# f9p_rtk.net
KiCad netlist of a schematic drawn in EasyEDA
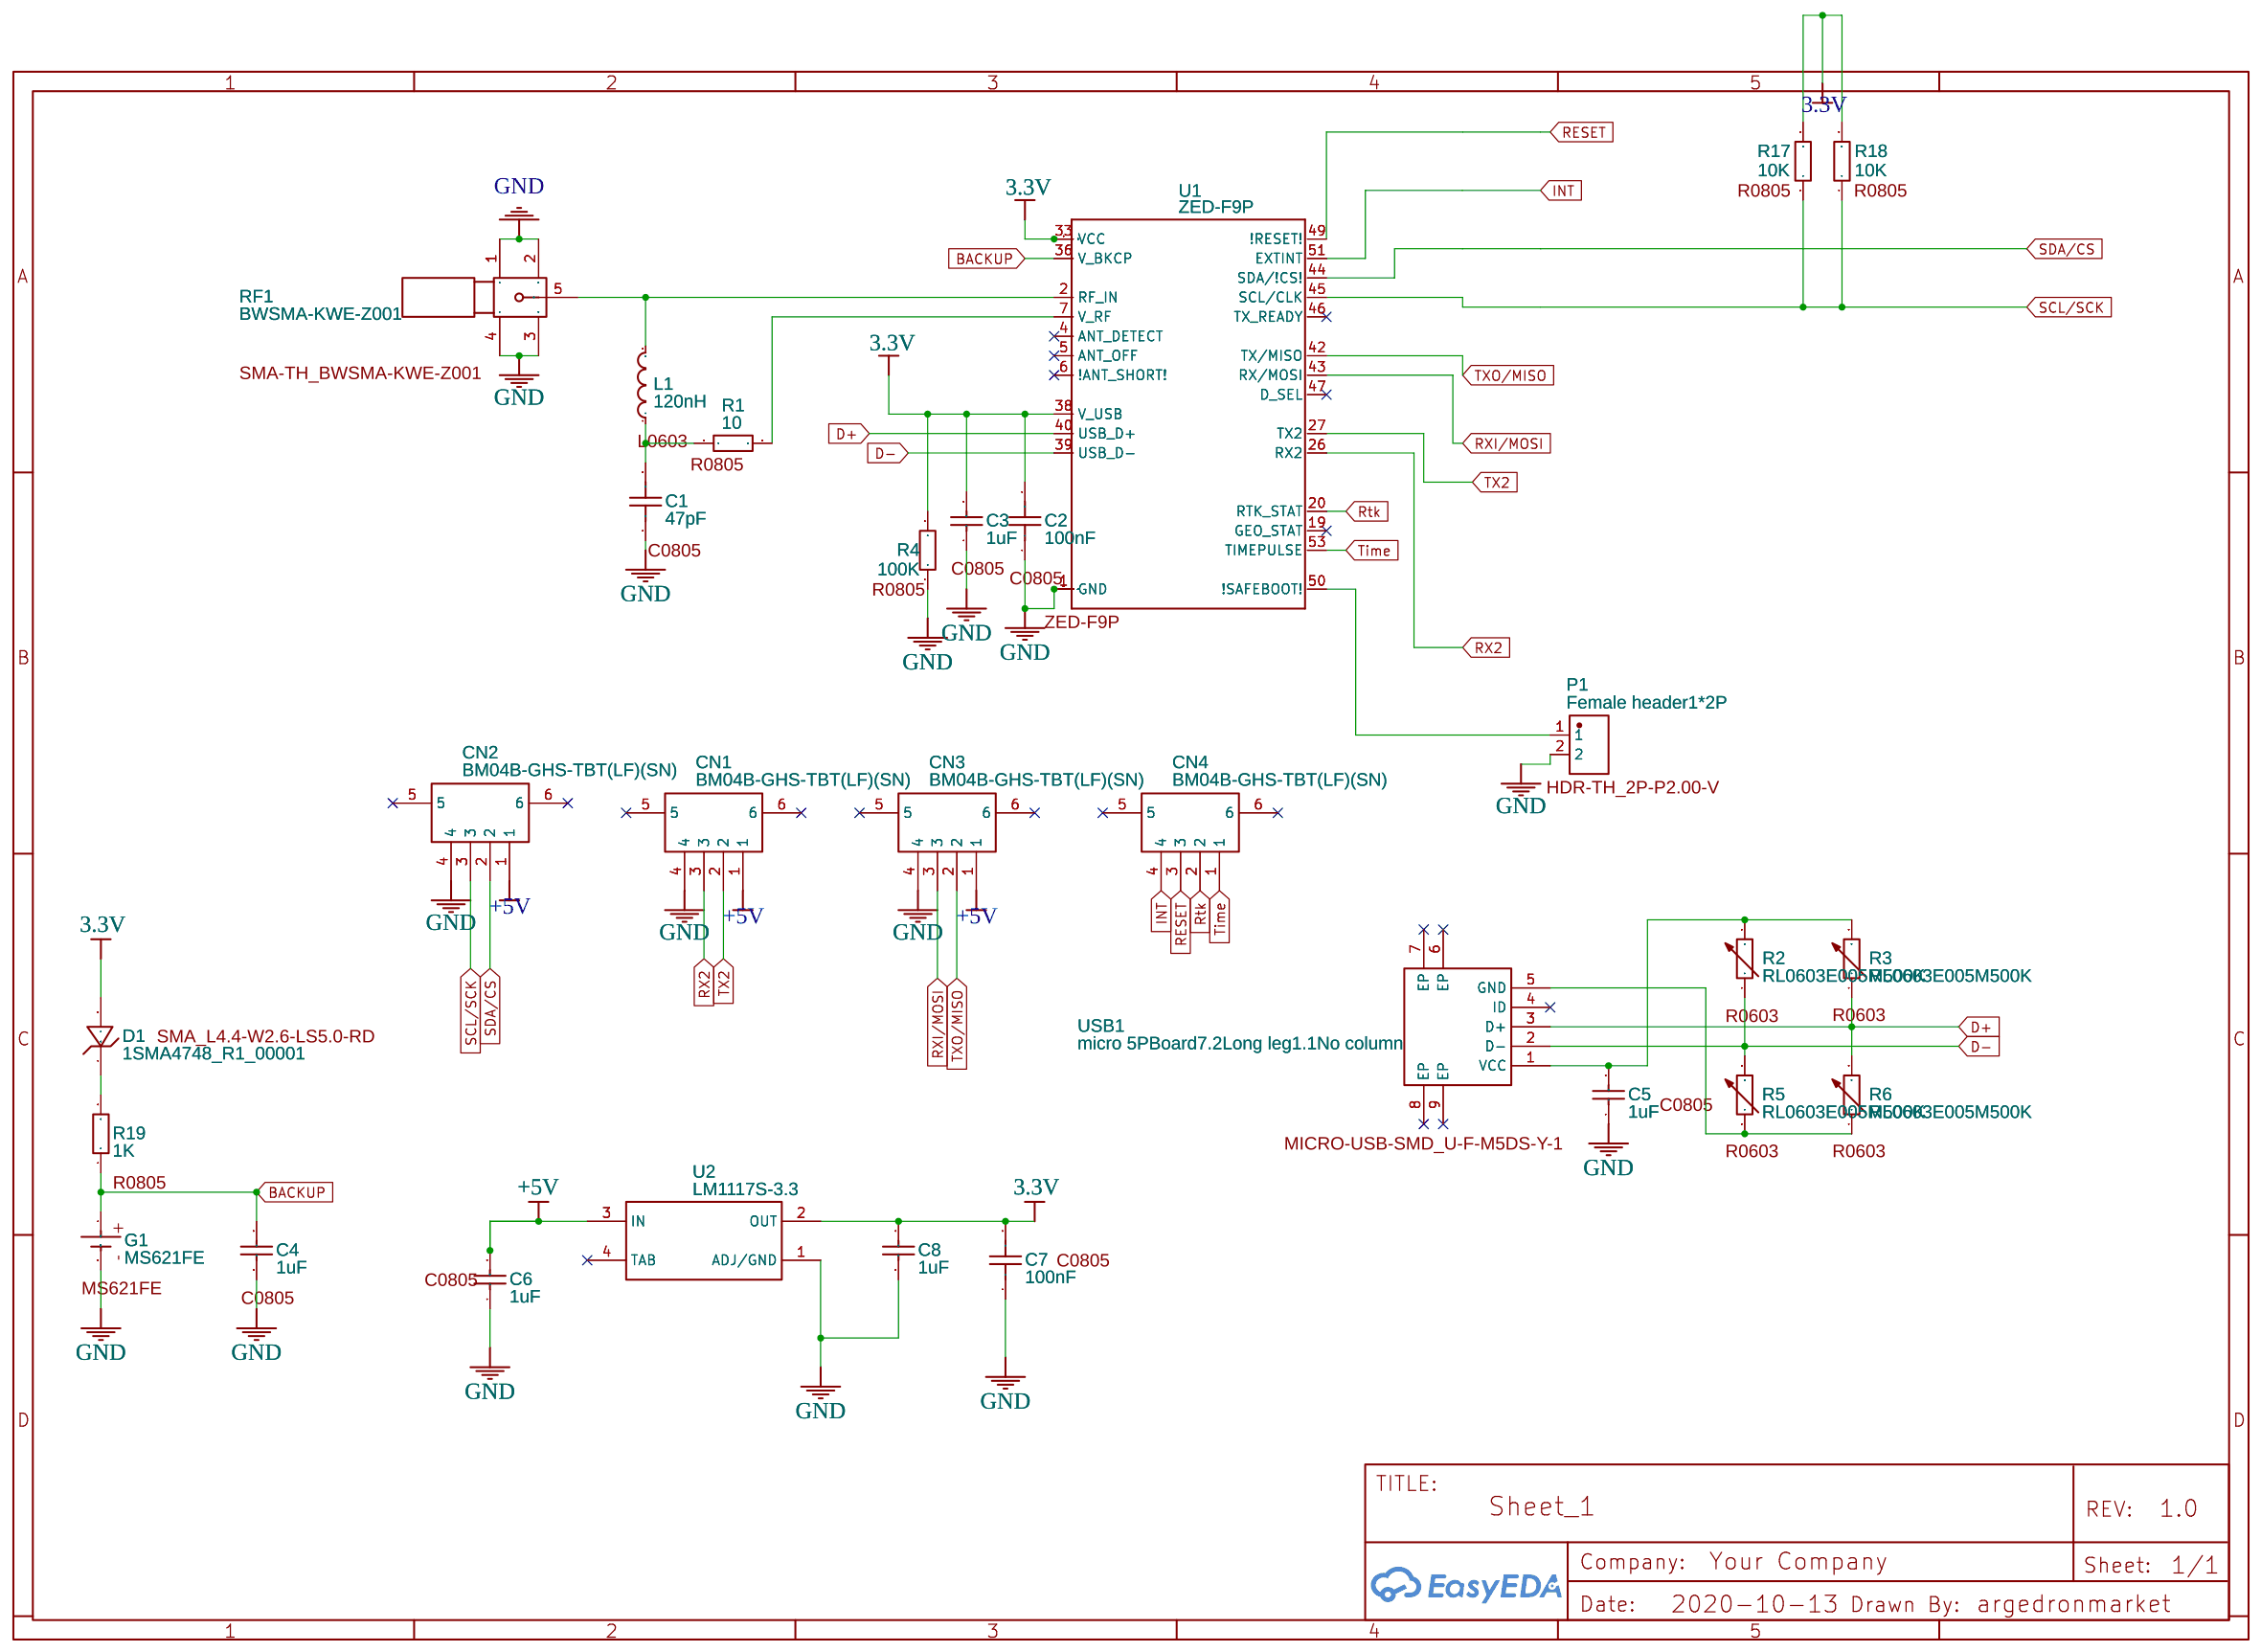
[diagram p0: schematic sheet]

(export (version "E")
  (design (tool "Eeschema 10.0.6"))
  (components
    (comp (ref "C1")
      (value "47pF")
      (fields
        (field (name "BOM_Manufacturer Part") "0805N470J500")
        (field (name "BOM_Supplier Part") "C123648")
      )
      (libsource (lib "") (part "0805N470J500"))
    )
    (comp (ref "C2")
      (value "100nF")
      (fields
        (field (name "BOM_Manufacturer Part") "TCC0805X7R104K101DT")
        (field (name "BOM_Supplier Part") "C344180")
      )
      (libsource (lib "") (part "TCC0805X7R104K101DT_1"))
    )
    (comp (ref "C3")
      (value "1uF")
      (fields
        (field (name "BOM_Manufacturer Part") "0805F105Z160")
        (field (name "BOM_Supplier Part") "C123629")
      )
      (libsource (lib "") (part "0805F105Z160"))
    )
    (comp (ref "C4")
      (value "1uF")
      (fields
        (field (name "BOM_Manufacturer Part") "0805F105Z160")
        (field (name "BOM_Supplier Part") "C123629")
      )
      (libsource (lib "") (part "0805F105Z160"))
    )
    (comp (ref "C5")
      (value "1uF")
      (fields
        (field (name "BOM_Manufacturer Part") "0805F105Z160")
        (field (name "BOM_Supplier Part") "C123629")
      )
      (libsource (lib "") (part "0805F105Z160_1"))
    )
    (comp (ref "C6")
      (value "1uF")
      (fields
        (field (name "BOM_Manufacturer Part") "0805F105Z160")
        (field (name "BOM_Supplier Part") "C123629")
      )
      (libsource (lib "") (part "0805F105Z160_2"))
    )
    (comp (ref "C7")
      (value "100nF")
      (fields
        (field (name "BOM_Manufacturer Part") "TCC0805X7R104K101DT")
        (field (name "BOM_Supplier Part") "C344180")
      )
      (libsource (lib "") (part "TCC0805X7R104K101DT"))
    )
    (comp (ref "C8")
      (value "1uF")
      (fields
        (field (name "BOM_Manufacturer Part") "0805F105Z160")
        (field (name "BOM_Supplier Part") "C123629")
      )
      (libsource (lib "") (part "0805F105Z160_3"))
    )
    (comp (ref "CN1")
      (value "BM04B-GHS-TBT(LF)(SN)")
      (fields (field (name "BOM_Supplier Part") "C161692"))
      (libsource (lib "") (part "BM04B-GHS-TBT(LF)(SN)"))
    )
    (comp (ref "CN2")
      (value "BM04B-GHS-TBT(LF)(SN)")
      (fields (field (name "BOM_Supplier Part") "C161692"))
      (libsource (lib "") (part "BM04B-GHS-TBT(LF)(SN)"))
    )
    (comp (ref "CN3")
      (value "BM04B-GHS-TBT(LF)(SN)")
      (fields (field (name "BOM_Supplier Part") "C161692"))
      (libsource (lib "") (part "BM04B-GHS-TBT(LF)(SN)"))
    )
    (comp (ref "CN4")
      (value "BM04B-GHS-TBT(LF)(SN)")
      (fields (field (name "BOM_Supplier Part") "C161692"))
      (libsource (lib "") (part "BM04B-GHS-TBT(LF)(SN)"))
    )
    (comp (ref "D1")
      (value "1SMA4748_R1_00001")
      (fields (field (name "BOM_Supplier Part") "C268431"))
      (libsource (lib "") (part "1SMA4748_R1_00001"))
    )
    (comp (ref "G1") (value "MS621FE") (libsource (lib "") (part "MS621FE")))
    (comp (ref "L1")
      (value "120nH")
      (fields
        (field (name "BOM_Manufacturer Part") "CI1608AR12K")
        (field (name "BOM_Supplier Part") "C107493")
      )
      (libsource (lib "") (part "CI1608AR12K"))
    )
    (comp (ref "P1")
      (value "Female header1*2P")
      (fields (field (name "BOM_Supplier Part") "C66509"))
      (libsource (lib "") (part "Female header1*2P"))
    )
    (comp (ref "R1")
      (value "10")
      (fields
        (field (name "BOM_Manufacturer Part") "CR0805F810R0G")
        (field (name "BOM_Supplier Part") "C101420")
      )
      (libsource (lib "") (part "CR0805F810R0G"))
    )
    (comp (ref "R2")
      (value "RL0603E005M500K")
      (fields (field (name "BOM_Supplier Part") "C20960"))
      (libsource (lib "") (part "RL0603E005M500K_1"))
    )
    (comp (ref "R3")
      (value "RL0603E005M500K")
      (fields (field (name "BOM_Supplier Part") "C20960"))
      (libsource (lib "") (part "RL0603E005M500K"))
    )
    (comp (ref "R4")
      (value "100K")
      (fields
        (field (name "BOM_Manufacturer Part") "RS-05K1003FT")
        (field (name "BOM_Supplier Part") "C118847")
      )
      (libsource (lib "") (part "RS-05K1003FT"))
    )
    (comp (ref "R5")
      (value "RL0603E005M500K")
      (fields (field (name "BOM_Supplier Part") "C20960"))
      (libsource (lib "") (part "RL0603E005M500K"))
    )
    (comp (ref "R6")
      (value "RL0603E005M500K")
      (fields (field (name "BOM_Supplier Part") "C20960"))
      (libsource (lib "") (part "RL0603E005M500K"))
    )
    (comp (ref "R17")
      (value "10K")
      (fields
        (field (name "BOM_Manufacturer Part") "RS-05K1002FT")
        (field (name "BOM_Supplier Part") "C115309")
      )
      (libsource (lib "") (part "RS-05K1002FT"))
    )
    (comp (ref "R18")
      (value "10K")
      (fields
        (field (name "BOM_Manufacturer Part") "RS-05K1002FT")
        (field (name "BOM_Supplier Part") "C115309")
      )
      (libsource (lib "") (part "RS-05K1002FT_1"))
    )
    (comp (ref "R19")
      (value "1K")
      (fields
        (field (name "BOM_Manufacturer Part") "ARG05FTC1001")
        (field (name "BOM_Supplier Part") "C218388")
      )
      (libsource (lib "") (part "ARG05FTC1001"))
    )
    (comp (ref "RF1")
      (value "BWSMA-KWE-Z001")
      (fields (field (name "BOM_Supplier Part") "C496551"))
      (libsource (lib "") (part "BWSMA-KWE-Z001"))
    )
    (comp (ref "U1") (value "ZED-F9P") (libsource (lib "") (part "ZED-F9P")))
    (comp (ref "U2")
      (value "LM1117S-3.3")
      (fields (field (name "BOM_Supplier Part") "C126027"))
      (libsource (lib "") (part "LM1117S-3.3"))
    )
    (comp (ref "USB1")
      (value "micro 5PBoard7.2Long leg1.1No column")
      (fields (field (name "BOM_Supplier Part") "C40951"))
      (libsource (lib "") (part "micro 5PBoard7.2Long leg1.1No column"))
    )
  )
  (nets
    (net (code "1") (name "+5V") (class "Default")
      (node (ref "C6") (pin "2") (pinfunction "2_2") (pintype "input"))
      (node (ref "CN1") (pin "1") (pinfunction "1_1") (pintype "unspecified"))
      (node (ref "CN2") (pin "1") (pinfunction "1_1") (pintype "unspecified"))
      (node (ref "CN3") (pin "1") (pinfunction "1_1") (pintype "unspecified"))
      (node (ref "U2") (pin "3") (pinfunction "IN_3") (pintype "passive"))
    )
    (net (code "2") (name "3.3V") (class "Default")
      (node (ref "C2") (pin "2") (pinfunction "2_2") (pintype "unspecified"))
      (node (ref "C3") (pin "2") (pinfunction "2_2") (pintype "input"))
      (node (ref "C7") (pin "2") (pinfunction "2_2") (pintype "unspecified"))
      (node (ref "C8") (pin "2") (pinfunction "2_2") (pintype "input"))
      (node (ref "D1") (pin "2") (pinfunction "A_2") (pintype "unspecified"))
      (node (ref "R17") (pin "2") (pinfunction "2_2") (pintype "input"))
      (node (ref "R18") (pin "2") (pinfunction "2_2") (pintype "input"))
      (node (ref "R4") (pin "2") (pinfunction "2_2") (pintype "input"))
      (node (ref "U1") (pin "33") (pinfunction "VCC_33") (pintype "bidirectional"))
      (node (ref "U1") (pin "34") (pinfunction "VCC_34") (pintype "bidirectional"))
      (node (ref "U1") (pin "38") (pinfunction "V_USB_38") (pintype "bidirectional"))
      (node (ref "U2") (pin "2") (pinfunction "OUT_2") (pintype "passive"))
    )
    (net (code "3") (name "BACKUP") (class "Default")
      (node (ref "C4") (pin "2") (pinfunction "2_2") (pintype "input"))
      (node (ref "G1") (pin "1") (pinfunction "Plus_1") (pintype "unspecified"))
      (node (ref "R19") (pin "1") (pinfunction "1_1") (pintype "unspecified"))
      (node (ref "U1") (pin "36") (pinfunction "V_BKCP_36") (pintype "bidirectional"))
    )
    (net (code "4") (name "D+") (class "Default")
      (node (ref "R3") (pin "1") (pinfunction "1_1") (pintype "unspecified"))
      (node (ref "R6") (pin "2") (pinfunction "2_2") (pintype "unspecified"))
      (node (ref "U1") (pin "40") (pinfunction "USB_D+_40") (pintype "bidirectional"))
      (node (ref "USB1") (pin "3") (pinfunction "D+_3") (pintype "unspecified"))
    )
    (net (code "5") (name "D-") (class "Default")
      (node (ref "R2") (pin "1") (pinfunction "1_1") (pintype "unspecified"))
      (node (ref "R5") (pin "2") (pinfunction "2_2") (pintype "unspecified"))
      (node (ref "U1") (pin "39") (pinfunction "USB_D-_39") (pintype "bidirectional"))
      (node (ref "USB1") (pin "2") (pinfunction "D-_2") (pintype "unspecified"))
    )
    (net (code "6") (name "GND") (class "Default")
      (node (ref "C1") (pin "1") (pinfunction "1_1") (pintype "unspecified"))
      (node (ref "C2") (pin "1") (pinfunction "1_1") (pintype "unspecified"))
      (node (ref "C3") (pin "1") (pinfunction "1_1") (pintype "input"))
      (node (ref "C4") (pin "1") (pinfunction "1_1") (pintype "input"))
      (node (ref "C5") (pin "1") (pinfunction "1_1") (pintype "input"))
      (node (ref "C6") (pin "1") (pinfunction "1_1") (pintype "input"))
      (node (ref "C7") (pin "1") (pinfunction "1_1") (pintype "unspecified"))
      (node (ref "C8") (pin "1") (pinfunction "1_1") (pintype "input"))
      (node (ref "CN1") (pin "4") (pinfunction "4_4") (pintype "unspecified"))
      (node (ref "CN2") (pin "4") (pinfunction "4_4") (pintype "unspecified"))
      (node (ref "CN3") (pin "4") (pinfunction "4_4") (pintype "unspecified"))
      (node (ref "G1") (pin "2") (pinfunction "Minus_2") (pintype "unspecified"))
      (node (ref "P1") (pin "2") (pinfunction "2_2") (pintype "unspecified"))
      (node (ref "R4") (pin "1") (pinfunction "1_1") (pintype "input"))
      (node (ref "RF1") (pin "1") (pinfunction "1_1") (pintype "unspecified"))
      (node (ref "RF1") (pin "2") (pinfunction "2_2") (pintype "unspecified"))
      (node (ref "RF1") (pin "3") (pinfunction "3_3") (pintype "unspecified"))
      (node (ref "RF1") (pin "4") (pinfunction "4_4") (pintype "unspecified"))
      (node (ref "U1") (pin "1") (pinfunction "GND_1") (pintype "bidirectional"))
      (node (ref "U1") (pin "100") (pinfunction "GND_100") (pintype "bidirectional"))
      (node (ref "U1") (pin "101") (pinfunction "GND_101") (pintype "bidirectional"))
      (node (ref "U1") (pin "102") (pinfunction "GND_102") (pintype "bidirectional"))
      (node (ref "U1") (pin "12") (pinfunction "GND_12") (pintype "bidirectional"))
      (node (ref "U1") (pin "14") (pinfunction "GND_14") (pintype "bidirectional"))
      (node (ref "U1") (pin "3") (pinfunction "GND_3") (pintype "bidirectional"))
      (node (ref "U1") (pin "32") (pinfunction "GND_32") (pintype "bidirectional"))
      (node (ref "U1") (pin "37") (pinfunction "GND_37") (pintype "bidirectional"))
      (node (ref "U1") (pin "41") (pinfunction "GND_41") (pintype "bidirectional"))
      (node (ref "U1") (pin "48") (pinfunction "GND_48") (pintype "bidirectional"))
      (node (ref "U1") (pin "55") (pinfunction "GND_55") (pintype "bidirectional"))
      (node (ref "U1") (pin "56") (pinfunction "GND_56") (pintype "bidirectional"))
      (node (ref "U1") (pin "57") (pinfunction "GND_57") (pintype "bidirectional"))
      (node (ref "U1") (pin "58") (pinfunction "GND_58") (pintype "bidirectional"))
      (node (ref "U1") (pin "59") (pinfunction "GND_59") (pintype "bidirectional"))
      (node (ref "U1") (pin "60") (pinfunction "GND_60") (pintype "bidirectional"))
      (node (ref "U1") (pin "61") (pinfunction "GND_61") (pintype "bidirectional"))
      (node (ref "U1") (pin "62") (pinfunction "GND_62") (pintype "bidirectional"))
      (node (ref "U1") (pin "63") (pinfunction "GND_63") (pintype "bidirectional"))
      (node (ref "U1") (pin "64") (pinfunction "GND_64") (pintype "bidirectional"))
      (node (ref "U1") (pin "65") (pinfunction "GND_65") (pintype "bidirectional"))
      (node (ref "U1") (pin "66") (pinfunction "GND_66") (pintype "bidirectional"))
      (node (ref "U1") (pin "67") (pinfunction "GND_67") (pintype "bidirectional"))
      (node (ref "U1") (pin "68") (pinfunction "GND_68") (pintype "bidirectional"))
      (node (ref "U1") (pin "69") (pinfunction "GND_69") (pintype "bidirectional"))
      (node (ref "U1") (pin "70") (pinfunction "GND_70") (pintype "bidirectional"))
      (node (ref "U1") (pin "71") (pinfunction "GND_71") (pintype "bidirectional"))
      (node (ref "U1") (pin "72") (pinfunction "GND_72") (pintype "bidirectional"))
      (node (ref "U1") (pin "73") (pinfunction "GND_73") (pintype "bidirectional"))
      (node (ref "U1") (pin "74") (pinfunction "GND_74") (pintype "bidirectional"))
      (node (ref "U1") (pin "75") (pinfunction "GND_75") (pintype "bidirectional"))
      (node (ref "U1") (pin "76") (pinfunction "GND_76") (pintype "bidirectional"))
      (node (ref "U1") (pin "77") (pinfunction "GND_77") (pintype "bidirectional"))
      (node (ref "U1") (pin "78") (pinfunction "GND_78") (pintype "bidirectional"))
      (node (ref "U1") (pin "79") (pinfunction "GND_79") (pintype "bidirectional"))
      (node (ref "U1") (pin "80") (pinfunction "GND_80") (pintype "bidirectional"))
      (node (ref "U1") (pin "81") (pinfunction "GND_81") (pintype "bidirectional"))
      (node (ref "U1") (pin "82") (pinfunction "GND_82") (pintype "bidirectional"))
      (node (ref "U1") (pin "83") (pinfunction "GND_83") (pintype "bidirectional"))
      (node (ref "U1") (pin "84") (pinfunction "GND_84") (pintype "bidirectional"))
      (node (ref "U1") (pin "85") (pinfunction "GND_85") (pintype "bidirectional"))
      (node (ref "U1") (pin "86") (pinfunction "GND_86") (pintype "bidirectional"))
      (node (ref "U1") (pin "87") (pinfunction "GND_87") (pintype "bidirectional"))
      (node (ref "U1") (pin "88") (pinfunction "GND_88") (pintype "bidirectional"))
      (node (ref "U1") (pin "89") (pinfunction "GND_89") (pintype "bidirectional"))
      (node (ref "U1") (pin "90") (pinfunction "GND_90") (pintype "bidirectional"))
      (node (ref "U1") (pin "91") (pinfunction "GND_91") (pintype "bidirectional"))
      (node (ref "U1") (pin "92") (pinfunction "GND_92") (pintype "bidirectional"))
      (node (ref "U1") (pin "93") (pinfunction "GND_93") (pintype "bidirectional"))
      (node (ref "U1") (pin "94") (pinfunction "GND_94") (pintype "bidirectional"))
      (node (ref "U1") (pin "95") (pinfunction "GND_95") (pintype "bidirectional"))
      (node (ref "U1") (pin "96") (pinfunction "GND_96") (pintype "bidirectional"))
      (node (ref "U1") (pin "97") (pinfunction "GND_97") (pintype "bidirectional"))
      (node (ref "U1") (pin "98") (pinfunction "GND_98") (pintype "bidirectional"))
      (node (ref "U1") (pin "99") (pinfunction "GND_99") (pintype "bidirectional"))
      (node (ref "U2") (pin "1") (pinfunction "ADJ/GND_1") (pintype "unspecified"))
    )
    (net (code "7") (name "INT") (class "Default")
      (node (ref "CN4") (pin "4") (pinfunction "4_4") (pintype "unspecified"))
      (node (ref "U1") (pin "51") (pinfunction "EXTINT_51") (pintype "bidirectional"))
    )
    (net (code "8") (name "Net-(C1-Pad2)") (class "Default")
      (node (ref "C1") (pin "2") (pinfunction "2_2") (pintype "unspecified"))
      (node (ref "L1") (pin "1") (pinfunction "1_1") (pintype "unspecified"))
      (node (ref "R1") (pin "1") (pinfunction "1_1") (pintype "input"))
    )
    (net (code "9") (name "Net-(D1-C)") (class "Default")
      (node (ref "D1") (pin "1") (pinfunction "C_1") (pintype "unspecified"))
      (node (ref "R19") (pin "2") (pinfunction "2_2") (pintype "unspecified"))
    )
    (net (code "10") (name "Net-(U1-!SAFEBOOT!)") (class "Default")
      (node (ref "P1") (pin "1") (pinfunction "1_1") (pintype "unspecified"))
      (node (ref "U1") (pin "50") (pinfunction "!SAFEBOOT!_50") (pintype "bidirectional"))
    )
    (net (code "11") (name "Net-(U1-RF_IN)") (class "Default")
      (node (ref "L1") (pin "2") (pinfunction "2_2") (pintype "unspecified"))
      (node (ref "RF1") (pin "5") (pinfunction "5_5") (pintype "unspecified"))
      (node (ref "U1") (pin "2") (pinfunction "RF_IN_2") (pintype "bidirectional"))
    )
    (net (code "12") (name "Net-(U1-V_RF)") (class "Default")
      (node (ref "R1") (pin "2") (pinfunction "2_2") (pintype "input"))
      (node (ref "U1") (pin "7") (pinfunction "V_RF_7") (pintype "bidirectional"))
    )
    (net (code "13") (name "Net-(USB1-GND)") (class "Default")
      (node (ref "R5") (pin "1") (pinfunction "1_1") (pintype "unspecified"))
      (node (ref "R6") (pin "1") (pinfunction "1_1") (pintype "unspecified"))
      (node (ref "USB1") (pin "5") (pinfunction "GND_5") (pintype "unspecified"))
    )
    (net (code "14") (name "Net-(USB1-VCC)") (class "Default")
      (node (ref "C5") (pin "2") (pinfunction "2_2") (pintype "input"))
      (node (ref "R2") (pin "2") (pinfunction "2_2") (pintype "unspecified"))
      (node (ref "R3") (pin "2") (pinfunction "2_2") (pintype "unspecified"))
      (node (ref "USB1") (pin "1") (pinfunction "VCC_1") (pintype "unspecified"))
    )
    (net (code "15") (name "RESET") (class "Default")
      (node (ref "CN4") (pin "3") (pinfunction "3_3") (pintype "unspecified"))
      (node (ref "U1") (pin "49") (pinfunction "!RESET!_49") (pintype "bidirectional"))
    )
    (net (code "16") (name "RX2") (class "Default")
      (node (ref "CN1") (pin "3") (pinfunction "3_3") (pintype "unspecified"))
      (node (ref "U1") (pin "26") (pinfunction "RX2_26") (pintype "bidirectional"))
    )
    (net (code "17") (name "RXI{slash}MOSI") (class "Default")
      (node (ref "CN3") (pin "3") (pinfunction "3_3") (pintype "unspecified"))
      (node (ref "U1") (pin "43") (pinfunction "RX/MOSI_43") (pintype "bidirectional"))
    )
    (net (code "18") (name "Rtk") (class "Default")
      (node (ref "CN4") (pin "2") (pinfunction "2_2") (pintype "unspecified"))
      (node (ref "U1") (pin "20") (pinfunction "RTK_STAT_20") (pintype "bidirectional"))
    )
    (net (code "19") (name "SCL{slash}SCK") (class "Default")
      (node (ref "CN2") (pin "3") (pinfunction "3_3") (pintype "unspecified"))
      (node (ref "R17") (pin "1") (pinfunction "1_1") (pintype "input"))
      (node (ref "R18") (pin "1") (pinfunction "1_1") (pintype "input"))
      (node (ref "U1") (pin "45") (pinfunction "SCL/CLK_45") (pintype "bidirectional"))
    )
    (net (code "20") (name "SDA{slash}CS") (class "Default")
      (node (ref "CN2") (pin "2") (pinfunction "2_2") (pintype "unspecified"))
      (node (ref "U1") (pin "44") (pinfunction "SDA/!CS!_44") (pintype "bidirectional"))
    )
    (net (code "21") (name "TX2") (class "Default")
      (node (ref "CN1") (pin "2") (pinfunction "2_2") (pintype "unspecified"))
      (node (ref "U1") (pin "27") (pinfunction "TX2_27") (pintype "bidirectional"))
    )
    (net (code "22") (name "TXO{slash}MISO") (class "Default")
      (node (ref "CN3") (pin "2") (pinfunction "2_2") (pintype "unspecified"))
      (node (ref "U1") (pin "42") (pinfunction "TX/MISO_42") (pintype "bidirectional"))
    )
    (net (code "23") (name "Time") (class "Default")
      (node (ref "CN4") (pin "1") (pinfunction "1_1") (pintype "unspecified"))
      (node (ref "U1") (pin "53") (pinfunction "TIMEPULSE_53") (pintype "bidirectional"))
    )
    (net (code "24") (name "unconnected-(CN1-Pad5)") (class "Default")
      (node (ref "CN1") (pin "5") (pinfunction "5_5") (pintype "unspecified+no_connect"))
    )
    (net (code "25") (name "unconnected-(CN1-Pad6)") (class "Default")
      (node (ref "CN1") (pin "6") (pinfunction "6_6") (pintype "unspecified+no_connect"))
    )
    (net (code "26") (name "unconnected-(CN2-Pad5)") (class "Default")
      (node (ref "CN2") (pin "5") (pinfunction "5_5") (pintype "unspecified+no_connect"))
    )
    (net (code "27") (name "unconnected-(CN2-Pad6)") (class "Default")
      (node (ref "CN2") (pin "6") (pinfunction "6_6") (pintype "unspecified+no_connect"))
    )
    (net (code "28") (name "unconnected-(CN3-Pad5)") (class "Default")
      (node (ref "CN3") (pin "5") (pinfunction "5_5") (pintype "unspecified+no_connect"))
    )
    (net (code "29") (name "unconnected-(CN3-Pad6)") (class "Default")
      (node (ref "CN3") (pin "6") (pinfunction "6_6") (pintype "unspecified+no_connect"))
    )
    (net (code "30") (name "unconnected-(CN4-Pad5)") (class "Default")
      (node (ref "CN4") (pin "5") (pinfunction "5_5") (pintype "unspecified+no_connect"))
    )
    (net (code "31") (name "unconnected-(CN4-Pad6)") (class "Default")
      (node (ref "CN4") (pin "6") (pinfunction "6_6") (pintype "unspecified+no_connect"))
    )
    (net (code "32") (name "unconnected-(U1-!ANT_SHORT!-Pad6)") (class "Default")
      (node (ref "U1") (pin "6") (pinfunction "!ANT_SHORT!_6") (pintype "bidirectional+no_connect"))
    )
    (net (code "33") (name "unconnected-(U1-ANT_DETECT-Pad4)") (class "Default")
      (node (ref "U1") (pin "4") (pinfunction "ANT_DETECT_4") (pintype "bidirectional+no_connect"))
    )
    (net (code "34") (name "unconnected-(U1-ANT_OFF-Pad5)") (class "Default")
      (node (ref "U1") (pin "5") (pinfunction "ANT_OFF_5") (pintype "bidirectional+no_connect"))
    )
    (net (code "35") (name "unconnected-(U1-D_SEL-Pad47)") (class "Default")
      (node (ref "U1") (pin "47") (pinfunction "D_SEL_47") (pintype "bidirectional+no_connect"))
    )
    (net (code "36") (name "unconnected-(U1-GEO_STAT-Pad19)") (class "Default")
      (node (ref "U1") (pin "19") (pinfunction "GEO_STAT_19") (pintype "bidirectional+no_connect"))
    )
    (net (code "37") (name "unconnected-(U1-TX_READY-Pad46)") (class "Default")
      (node (ref "U1") (pin "46") (pinfunction "TX_READY_46") (pintype "bidirectional+no_connect"))
    )
    (net (code "38") (name "unconnected-(U2-TAB-Pad4)") (class "Default")
      (node (ref "U2") (pin "4") (pinfunction "TAB_4") (pintype "passive+no_connect"))
    )
    (net (code "39") (name "unconnected-(USB1-EP-Pad6)") (class "Default")
      (node (ref "USB1") (pin "6") (pinfunction "EP_6") (pintype "unspecified+no_connect"))
    )
    (net (code "40") (name "unconnected-(USB1-EP-Pad7)") (class "Default")
      (node (ref "USB1") (pin "7") (pinfunction "EP_7") (pintype "unspecified+no_connect"))
    )
    (net (code "41") (name "unconnected-(USB1-EP-Pad8)") (class "Default")
      (node (ref "USB1") (pin "8") (pinfunction "EP_8") (pintype "unspecified+no_connect"))
    )
    (net (code "42") (name "unconnected-(USB1-EP-Pad9)") (class "Default")
      (node (ref "USB1") (pin "9") (pinfunction "EP_9") (pintype "unspecified+no_connect"))
    )
    (net (code "43") (name "unconnected-(USB1-ID-Pad4)") (class "Default")
      (node (ref "USB1") (pin "4") (pinfunction "ID_4") (pintype "unspecified+no_connect"))
    )
  )
)
